# LEDs.net
KiCad netlist of a schematic drawn in Altium Designer
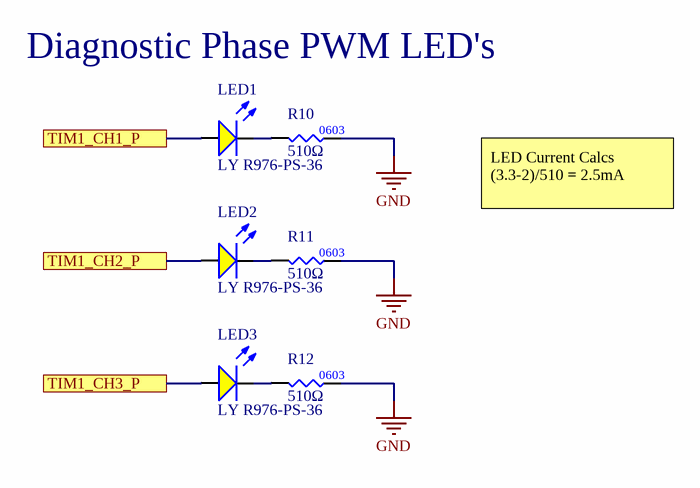
[diagram p0: LEDs.SchDoc]

(export (version "E")
  (design (tool "Eeschema 10.0.6"))
  (components
    (comp (ref "LED1")
      (value "LED_YELLOW")
      (footprint "LED_0805_YELLOW")
      (description "LED YELLOW DIFFUSED 0805 SMD")
      (fields (field (name "MANUFACTURER PART NUMBER 1") "LY R976-PS-36"))
      (libsource (lib "UWRT_Schematic_Library_2020") (part "LED_YELLOW"))
    )
    (comp (ref "LED2")
      (value "LED_YELLOW")
      (footprint "LED_0805_YELLOW")
      (description "LED YELLOW DIFFUSED 0805 SMD")
      (fields (field (name "MANUFACTURER PART NUMBER 1") "LY R976-PS-36"))
      (libsource (lib "UWRT_Schematic_Library_2020") (part "LED_YELLOW"))
    )
    (comp (ref "LED3")
      (value "LED_YELLOW")
      (footprint "LED_0805_YELLOW")
      (description "LED YELLOW DIFFUSED 0805 SMD")
      (fields (field (name "MANUFACTURER PART NUMBER 1") "LY R976-PS-36"))
      (libsource (lib "UWRT_Schematic_Library_2020") (part "LED_YELLOW"))
    )
    (comp (ref "R10")
      (value "510Ω")
      (footprint "RES0603")
      (description "RES 510 OHM 5% 1/10W 0603")
      (fields (field (name "Comment") "RES_510Ω_0603_5%"))
      (libsource (lib "UWRT_Schematic_Library_2020") (part "RES_510Ω_0603_5%"))
    )
    (comp (ref "R11")
      (value "510Ω")
      (footprint "RES0603")
      (description "RES 510 OHM 5% 1/10W 0603")
      (fields (field (name "Comment") "RES_510Ω_0603_5%"))
      (libsource (lib "UWRT_Schematic_Library_2020") (part "RES_510Ω_0603_5%"))
    )
    (comp (ref "R12")
      (value "510Ω")
      (footprint "RES0603")
      (description "RES 510 OHM 5% 1/10W 0603")
      (fields (field (name "Comment") "RES_510Ω_0603_5%"))
      (libsource (lib "UWRT_Schematic_Library_2020") (part "RES_510Ω_0603_5%"))
    )
  )
  (nets
    (net (code "1") (name "/TIM1_CH1_P") (class "Default")
      (node (ref "LED1") (pin "1") (pinfunction "A_1") (pintype "passive"))
    )
    (net (code "2") (name "/TIM1_CH2_P") (class "Default")
      (node (ref "LED2") (pin "1") (pinfunction "A_1") (pintype "passive"))
    )
    (net (code "3") (name "/TIM1_CH3_P") (class "Default")
      (node (ref "LED3") (pin "1") (pinfunction "A_1") (pintype "passive"))
    )
    (net (code "4") (name "GND") (class "Default")
      (node (ref "R10") (pin "2") (pinfunction "2_2") (pintype "passive"))
      (node (ref "R11") (pin "2") (pinfunction "2_2") (pintype "passive"))
      (node (ref "R12") (pin "2") (pinfunction "2_2") (pintype "passive"))
    )
    (net (code "5") (name "Net-(LED1-K)") (class "Default")
      (node (ref "LED1") (pin "2") (pinfunction "K_2") (pintype "passive"))
      (node (ref "R10") (pin "1") (pinfunction "1_1") (pintype "passive"))
    )
    (net (code "6") (name "Net-(LED2-K)") (class "Default")
      (node (ref "LED2") (pin "2") (pinfunction "K_2") (pintype "passive"))
      (node (ref "R11") (pin "1") (pinfunction "1_1") (pintype "passive"))
    )
    (net (code "7") (name "Net-(LED3-K)") (class "Default")
      (node (ref "LED3") (pin "2") (pinfunction "K_2") (pintype "passive"))
      (node (ref "R12") (pin "1") (pinfunction "1_1") (pintype "passive"))
    )
  )
)
